# Energy_Harvesting.net
KiCad netlist of a schematic drawn in Altium Designer
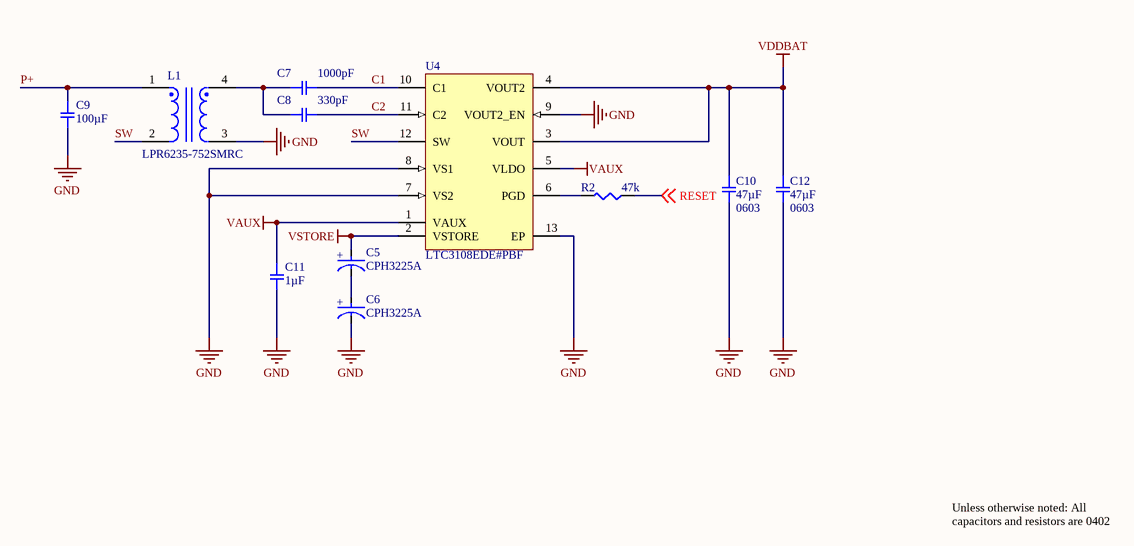
[diagram p0: Energy Harvesting.SchDoc]

(export (version "E")
  (design (tool "Eeschema 10.0.6"))
  (components
    (comp (ref "C5")
      (value "CPH3225A")
      (footprint "CPH3225A")
      (description "Supercapacitors / Ultracapacitors Reflow EDLC 3.3V, 11mF, 160 Ohm")
      (libsource (lib "Library") (part "CPH3225A"))
    )
    (comp (ref "C6")
      (value "CPH3225A")
      (footprint "CPH3225A")
      (description "Supercapacitors / Ultracapacitors Reflow EDLC 3.3V, 11mF, 160 Ohm")
      (libsource (lib "Library") (part "CPH3225A"))
    )
    (comp (ref "C7")
      (value "1000pF")
      (footprint "CAPC1005X03N")
      (description "CAP CER 1000PF 16V X5R 0402")
      (fields
        (field (name "DIGI-KEY PART NUMBER") "490-6308-1-ND")
        (field (name "PART NUMBER") "GRM155R61C102KA01D")
      )
      (libsource (lib "capacitor_murata_0402") (part "GRM155R61C102KA01D"))
    )
    (comp (ref "C8")
      (value "330pF")
      (footprint "CAPC1005X03N")
      (description "CAP CER 330PF 50V X7R 0402")
      (fields
        (field (name "DIGI-KEY PART NUMBER") "490-11424-1-ND")
        (field (name "PART NUMBER") "GRM155R71H331KA01J")
      )
      (libsource (lib "capacitor_murata_0402") (part "GRM155R71H331KA01J"))
    )
    (comp (ref "C9")
      (value "100µF")
      (footprint "CAPC2012X12N")
      (description "CAP CER 100UF 2.5V X6S 0805")
      (fields
        (field (name "DIGI-KEY PART NUMBER") "490-13977-1-ND")
        (field (name "PART NUMBER") "GRM21BC80E107ME15L")
      )
      (libsource (lib "capacitor_murata_0805") (part "GRM21BC80E107ME15L"))
    )
    (comp (ref "C10")
      (value "47µF")
      (footprint "CAPC1608X12N")
      (description "CAP CER 47UF 6.3V X5R 0603")
      (fields
        (field (name "DIGI-KEY PART NUMBER") "490-13211-1-ND")
        (field (name "PART NUMBER") "GRJ155R60J106ME11D")
        (field (name "PACKAGE / CASE") "0603")
      )
      (libsource (lib "capacitor_murata_0402") (part "GRJ155R60J106ME11D"))
    )
    (comp (ref "C11")
      (value "1µF")
      (footprint "CAPC1005X03N")
      (description "CAP CER 1UF 16V X5R 0402")
      (fields
        (field (name "DIGI-KEY PART NUMBER") "490-12255-1-ND")
        (field (name "PART NUMBER") "GRT155R61C105KE01D")
      )
      (libsource (lib "capacitor_murata_0402") (part "GRT155R61C105KE01D"))
    )
    (comp (ref "C12")
      (value "47µF")
      (footprint "CAPC1608X12N")
      (description "CAP CER 47UF 6.3V X5R 0603")
      (fields
        (field (name "DIGI-KEY PART NUMBER") "490-13211-1-ND")
        (field (name "PART NUMBER") "GRJ155R60J106ME11D")
        (field (name "PACKAGE / CASE") "0603")
      )
      (libsource (lib "capacitor_murata_0402") (part "GRJ155R60J106ME11D"))
    )
    (comp (ref "L1")
      (value "LPR6235-752SMRC")
      (footprint "LPR6235")
      (description "Gekoppelde smoorspoelen 7.5uH 75% 1.6A 316 Ohms 1:100")
      (libsource (lib "Library") (part "LPR6235-752SMRC"))
    )
    (comp (ref "R2")
      (value "47k")
      (footprint "CAPC1005X03N")
      (description "RES SMD 47K OHM 1% 1/10W 0402")
      (fields
        (field (name "PART NUMBER") "ERJ-2RKF4702X")
        (field (name "DIGI-KEY PART NUMBER") "P47.0KLCT-ND")
      )
      (libsource (lib "Panasonic_ERJ_0402") (part "ERJ-2RKF4702X"))
    )
    (comp (ref "U4")
      (value "LTC3108EDE#PBF")
      (footprint "LT-DE-12-05-08-1708_V")
      (description "Ultralow Voltage Step-Up Converter and Power Manager, 12-pin SON (DE-12), -40 to 125 degC, Pb-Free")
      (fields (field (name "MANUFACTURER") "Linear Technology"))
      (libsource (lib "Altium Content Vault") (part "LT-LTC3108-DE-UE-12"))
    )
  )
  (nets
    (net (code "1") (name "/C1") (class "Default")
      (node (ref "C7") (pin "2") (pinfunction "2_2") (pintype "passive"))
      (node (ref "U4") (pin "10") (pinfunction "C1_10") (pintype "power_in"))
    )
    (net (code "2") (name "/C2") (class "Default")
      (node (ref "C8") (pin "2") (pinfunction "2_2") (pintype "passive"))
      (node (ref "U4") (pin "11") (pinfunction "C2_11") (pintype "input"))
    )
    (net (code "3") (name "/P+") (class "Default")
      (node (ref "C9") (pin "1") (pinfunction "1_1") (pintype "passive"))
      (node (ref "L1") (pin "1") (pinfunction "1_1") (pintype "passive"))
    )
    (net (code "4") (name "/SW") (class "Default")
      (node (ref "L1") (pin "2") (pinfunction "2_2") (pintype "passive"))
      (node (ref "U4") (pin "12") (pinfunction "SW_12") (pintype "power_in"))
    )
    (net (code "5") (name "GND") (class "Default")
      (node (ref "C10") (pin "2") (pinfunction "2_2") (pintype "passive"))
      (node (ref "C11") (pin "2") (pinfunction "2_2") (pintype "passive"))
      (node (ref "C12") (pin "2") (pinfunction "2_2") (pintype "passive"))
      (node (ref "C6") (pin "2") (pinfunction "A_2") (pintype "passive"))
      (node (ref "C9") (pin "2") (pinfunction "2_2") (pintype "passive"))
      (node (ref "L1") (pin "3") (pinfunction "3_3") (pintype "passive"))
      (node (ref "U4") (pin "13") (pinfunction "EP_13") (pintype "power_in"))
      (node (ref "U4") (pin "7") (pinfunction "VS2_7") (pintype "input"))
      (node (ref "U4") (pin "8") (pinfunction "VS1_8") (pintype "input"))
      (node (ref "U4") (pin "9") (pinfunction "VOUT2_EN_9") (pintype "input"))
    )
    (net (code "6") (name "Net-(C5-A)") (class "Default")
      (node (ref "C5") (pin "2") (pinfunction "A_2") (pintype "passive"))
      (node (ref "C6") (pin "1") (pinfunction "C_1") (pintype "passive"))
    )
    (net (code "7") (name "Net-(C7-Pad1)") (class "Default")
      (node (ref "C7") (pin "1") (pinfunction "1_1") (pintype "passive"))
      (node (ref "C8") (pin "1") (pinfunction "1_1") (pintype "passive"))
      (node (ref "L1") (pin "4") (pinfunction "4_4") (pintype "passive"))
    )
    (net (code "8") (name "Net-(U4-PGD)") (class "Default")
      (node (ref "R2") (pin "2") (pinfunction "2_2") (pintype "passive"))
      (node (ref "U4") (pin "6") (pinfunction "PGD_6") (pintype "open_collector"))
    )
    (net (code "9") (name "RESET") (class "Default")
      (node (ref "R2") (pin "1") (pinfunction "1_1") (pintype "passive"))
    )
    (net (code "10") (name "VAUX") (class "Default")
      (node (ref "C11") (pin "1") (pinfunction "1_1") (pintype "passive"))
      (node (ref "U4") (pin "1") (pinfunction "VAUX_1") (pintype "power_in"))
      (node (ref "U4") (pin "5") (pinfunction "VLDO_5") (pintype "power_in"))
    )
    (net (code "11") (name "VDDBAT") (class "Default")
      (node (ref "C10") (pin "1") (pinfunction "1_1") (pintype "passive"))
      (node (ref "C12") (pin "1") (pinfunction "1_1") (pintype "passive"))
      (node (ref "U4") (pin "3") (pinfunction "VOUT_3") (pintype "power_in"))
      (node (ref "U4") (pin "4") (pinfunction "VOUT2_4") (pintype "power_in"))
    )
    (net (code "12") (name "VSTORE") (class "Default")
      (node (ref "C5") (pin "1") (pinfunction "C_1") (pintype "passive"))
      (node (ref "U4") (pin "2") (pinfunction "VSTORE_2") (pintype "power_in"))
    )
  )
)
